# Bluetooth_LMC9830SM.net
KiCad netlist of a schematic drawn in Altium Designer
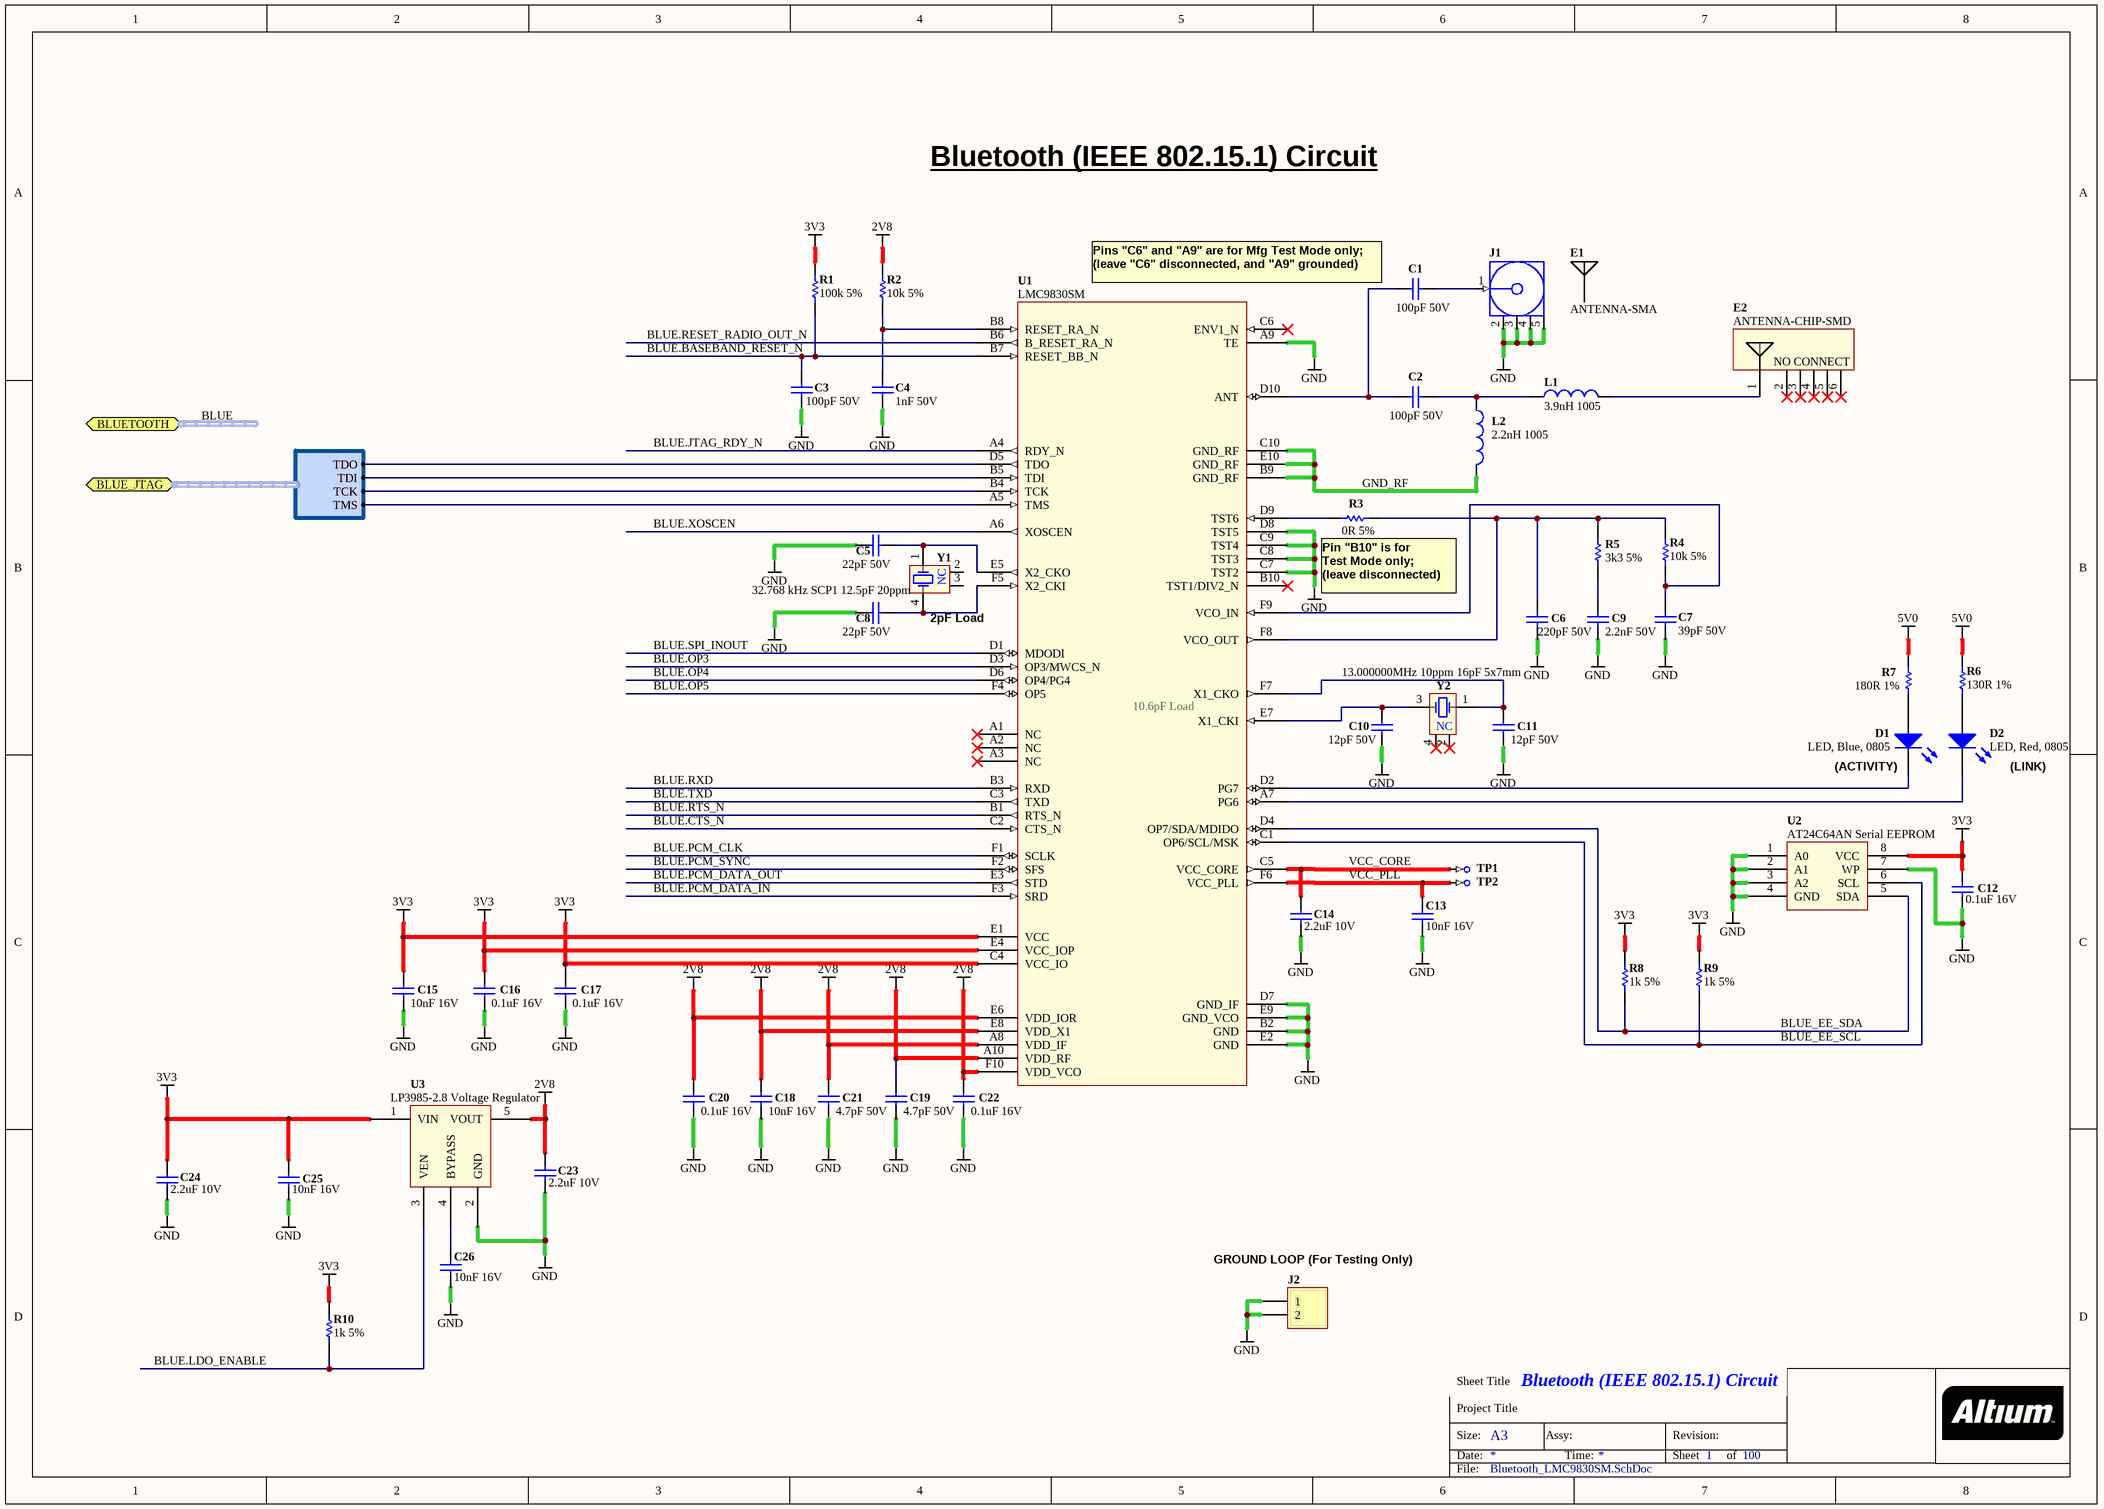
[diagram p0: Bluetooth_LMC9830SM.SchDoc]

(export (version "E")
  (design (tool "Eeschema 10.0.6"))
  (components
    (comp (ref "C1")
      (value "100pF 50V")
      (footprint "CAPC1005-STAR")
      (description "Capacitor, Ceramic, 100pF 5% 50V 0402 (1005) COG")
      (fields (field (name "TOLERANCE") "5 %"))
      (libsource (lib "AltiumDesignLibrary") (part "CAP-NP"))
    )
    (comp (ref "C2")
      (value "100pF 50V")
      (footprint "CAPC1005-STAR")
      (description "Capacitor, Ceramic, 100pF 5% 50V 0402 (1005) COG")
      (fields (field (name "TOLERANCE") "5 %"))
      (libsource (lib "AltiumDesignLibrary") (part "CAP-NP"))
    )
    (comp (ref "C3")
      (value "100pF 50V")
      (footprint "CAPC1005-STAR")
      (description "Capacitor, Ceramic, 100pF 5% 50V 0402 (1005) COG")
      (fields (field (name "TOLERANCE") "5 %"))
      (libsource (lib "AltiumDesignLibrary") (part "CAP-NP"))
    )
    (comp (ref "C4")
      (value "1nF 50V")
      (footprint "CAPC1005-STAR")
      (description "Capacitor, Ceramic, 1nF 10% 50V 0402 (1005) X7R")
      (fields (field (name "TOLERANCE") "10 %"))
      (libsource (lib "AltiumDesignLibrary") (part "CAP-NP"))
    )
    (comp (ref "C5")
      (value "22pF 50V")
      (footprint "CAPC1005-STAR")
      (description "Capacitor, Ceramic, 22pF 5% 50V 0402 (1005) COG")
      (fields (field (name "TOLERANCE") "5 %"))
      (libsource (lib "AltiumDesignLibrary") (part "CAP-NP"))
    )
    (comp (ref "C6")
      (value "220pF 50V")
      (footprint "CAPC1005-STAR")
      (description "Capacitor, Ceramic, 220pF 5% 50V 0402 (1005) COG")
      (fields (field (name "TOLERANCE") "5 %"))
      (libsource (lib "AltiumDesignLibrary") (part "CAP-NP"))
    )
    (comp (ref "C7")
      (value "39pF 50V")
      (footprint "CAPC1005-STAR")
      (description "Capacitor, Ceramic, 39pF 5% 50V 0402 (1005) COG")
      (fields (field (name "TOLERANCE") "5 %"))
      (libsource (lib "AltiumDesignLibrary") (part "CAP-NP"))
    )
    (comp (ref "C8")
      (value "22pF 50V")
      (footprint "CAPC1005-STAR")
      (description "Capacitor, Ceramic, 22pF 5% 50V 0402 (1005) COG")
      (fields (field (name "TOLERANCE") "5 %"))
      (libsource (lib "AltiumDesignLibrary") (part "CAP-NP"))
    )
    (comp (ref "C9")
      (value "2.2nF 50V")
      (footprint "CAPC1608-STAR")
      (description "Capacitor, Ceramic, 2.2nF 10% 50V 0603 (1608) X7R")
      (fields (field (name "TOLERANCE") "10 %"))
      (libsource (lib "AltiumDesignLibrary") (part "CAP-NP"))
    )
    (comp (ref "C10")
      (value "12pF 50V")
      (footprint "CAPC1005-STAR")
      (description "Capacitor, Ceramic, 12pF 2% 50V 0402 (1005) COG")
      (fields (field (name "TOLERANCE") "2 %"))
      (libsource (lib "AltiumDesignLibrary") (part "CAP-NP"))
    )
    (comp (ref "C11")
      (value "12pF 50V")
      (footprint "CAPC1005-STAR")
      (description "Capacitor, Ceramic, 12pF 2% 50V 0402 (1005) COG")
      (fields (field (name "TOLERANCE") "2 %"))
      (libsource (lib "AltiumDesignLibrary") (part "CAP-NP"))
    )
    (comp (ref "C12")
      (value "0.1uF 16V")
      (footprint "CAPC1005-STAR")
      (description "Capacitor, Ceramic, 0.1uF 10% 16V 0402 (1005) X7R")
      (fields (field (name "TOLERANCE") "10 %"))
      (libsource (lib "AltiumDesignLibrary") (part "CAP-NP"))
    )
    (comp (ref "C13")
      (value "10nF 16V")
      (footprint "CAPC1005-STAR")
      (description "Capacitor, Ceramic, 10nF 10% 16V 0402 (1005) X7R")
      (fields (field (name "TOLERANCE") "10 %"))
      (libsource (lib "AltiumDesignLibrary") (part "CAP-NP"))
    )
    (comp (ref "C14")
      (value "2.2uF 10V")
      (footprint "CAPC3216-STAR")
      (description "Capacitor, Ceramic, 2.2uF 10% 10V 1206 (3216) X7R")
      (fields (field (name "TOLERANCE") "10 %"))
      (libsource (lib "AltiumDesignLibrary") (part "CAP-NP"))
    )
    (comp (ref "C15")
      (value "10nF 16V")
      (footprint "CAPC1005-STAR")
      (description "Capacitor, Ceramic, 10nF 10% 16V 0402 (1005) X7R")
      (fields (field (name "TOLERANCE") "10 %"))
      (libsource (lib "AltiumDesignLibrary") (part "CAP-NP"))
    )
    (comp (ref "C16")
      (value "0.1uF 16V")
      (footprint "CAPC1005-STAR")
      (description "Capacitor, Ceramic, 0.1uF 10% 16V 0402 (1005) X7R")
      (fields (field (name "TOLERANCE") "10 %"))
      (libsource (lib "AltiumDesignLibrary") (part "CAP-NP"))
    )
    (comp (ref "C17")
      (value "0.1uF 16V")
      (footprint "CAPC1005-STAR")
      (description "Capacitor, Ceramic, 0.1uF 10% 16V 0402 (1005) X7R")
      (fields (field (name "TOLERANCE") "10 %"))
      (libsource (lib "AltiumDesignLibrary") (part "CAP-NP"))
    )
    (comp (ref "C18")
      (value "10nF 16V")
      (footprint "CAPC1005-STAR")
      (description "Capacitor, Ceramic, 10nF 10% 16V 0402 (1005) X7R")
      (fields (field (name "TOLERANCE") "10 %"))
      (libsource (lib "AltiumDesignLibrary") (part "CAP-NP"))
    )
    (comp (ref "C19")
      (value "4.7pF 50V")
      (footprint "CAPC1005-STAR")
      (description "Capacitor, Ceramic, 4.7pF 5% 50V 0402 (1005) COG")
      (fields (field (name "TOLERANCE") "5 %"))
      (libsource (lib "AltiumDesignLibrary") (part "CAP-NP"))
    )
    (comp (ref "C20")
      (value "0.1uF 16V")
      (footprint "CAPC1005-STAR")
      (description "Capacitor, Ceramic, 0.1uF 10% 16V 0402 (1005) X7R")
      (fields (field (name "TOLERANCE") "10 %"))
      (libsource (lib "AltiumDesignLibrary") (part "CAP-NP"))
    )
    (comp (ref "C21")
      (value "4.7pF 50V")
      (footprint "CAPC1005-STAR")
      (description "Capacitor, Ceramic, 4.7pF 5% 50V 0402 (1005) COG")
      (fields (field (name "TOLERANCE") "5 %"))
      (libsource (lib "AltiumDesignLibrary") (part "CAP-NP"))
    )
    (comp (ref "C22")
      (value "0.1uF 16V")
      (footprint "CAPC1005-STAR")
      (description "Capacitor, Ceramic, 0.1uF 10% 16V 0402 (1005) X7R")
      (fields (field (name "TOLERANCE") "10 %"))
      (libsource (lib "AltiumDesignLibrary") (part "CAP-NP"))
    )
    (comp (ref "C23")
      (value "2.2uF 10V")
      (footprint "CAPC3216-STAR")
      (description "Capacitor, Ceramic, 2.2uF 10% 10V 1206 (3216) X7R")
      (fields (field (name "TOLERANCE") "10 %"))
      (libsource (lib "AltiumDesignLibrary") (part "CAP-NP"))
    )
    (comp (ref "C24")
      (value "2.2uF 10V")
      (footprint "CAPC3216-STAR")
      (description "Capacitor, Ceramic, 2.2uF 10% 10V 1206 (3216) X7R")
      (fields (field (name "TOLERANCE") "10 %"))
      (libsource (lib "AltiumDesignLibrary") (part "CAP-NP"))
    )
    (comp (ref "C25")
      (value "10nF 16V")
      (footprint "CAPC1005-STAR")
      (description "Capacitor, Ceramic, 10nF 10% 16V 0402 (1005) X7R")
      (fields (field (name "TOLERANCE") "10 %"))
      (libsource (lib "AltiumDesignLibrary") (part "CAP-NP"))
    )
    (comp (ref "C26")
      (value "10nF 16V")
      (footprint "CAPC1005-STAR")
      (description "Capacitor, Ceramic, 10nF 10% 16V 0402 (1005) X7R")
      (fields (field (name "TOLERANCE") "10 %"))
      (libsource (lib "AltiumDesignLibrary") (part "CAP-NP"))
    )
    (comp (ref "D1")
      (value "LED, Blue, 0805")
      (footprint "LED2012-STAR")
      (description "LED, Blue 0805 (2012)")
      (libsource (lib "AltiumDesignLibrary") (part "DIO-LED-1S"))
    )
    (comp (ref "D2")
      (value "LED, Red, 0805")
      (footprint "LED2012-STAR")
      (description "LED, Red 0805 (2012) HSMH-C170")
      (libsource (lib "AltiumDesignLibrary") (part "DIO-LED-1S"))
    )
    (comp (ref "E1")
      (value "ANTENNA-SMA")
      (description "Antenna, 2.45GHz 1/4 Wave 50R SMA Antenna")
      (libsource (lib "AltiumDesignLibrary") (part "ANTENNA-0-PIN"))
    )
    (comp (ref "E2")
      (value "ANTENNA-CHIP-SMD")
      (footprint "ANTENNA-2-45GHZ-6PIN")
      (description "Antenna, 2.45GHz Chip SMD 5.5 X 7.35MM")
      (libsource (lib "AltiumDesignLibrary") (part "ANTENNA-6-PIN"))
    )
    (comp (ref "J1")
      (value "SMA 5-pin Vertical Jack 50R")
      (footprint "HDR-SMA-THD-5-PIN")
      (description "SMA RF Coaxial PCB Connector, 5-pin Through-hole, Vertical Mount Socket, 50 ohm impedance")
      (libsource (lib "AltiumDesignLibrary") (part "CON-HDR-COAXIAL-5-PIN"))
    )
    (comp (ref "J2")
      (value "1x2 HEADER MALE")
      (footprint "HDR1X2")
      (description "Header IDC, 2 x 1 Pin Vertical 2.54mm Pitch (Non-Boxed, Male)")
      (libsource (lib "AltiumDesignLibrary") (part "CON-HDR-1x2-STR"))
    )
    (comp (ref "L1")
      (value "3.9nH 1005")
      (footprint "INDC1005")
      (description "Inductor, Chip 3.9nH 300mA DCR=0.18 ohm, High Frequency 0402 (1005)")
      (libsource (lib "AltiumDesignLibrary") (part "IND"))
    )
    (comp (ref "L2")
      (value "2.2nH 1005")
      (footprint "INDC1005")
      (description "Inductor, Chip 2.2nH 300mA DCR=0.12 ohm, High Frequency 0402 (1005)")
      (libsource (lib "AltiumDesignLibrary") (part "IND"))
    )
    (comp (ref "R1")
      (value "100k 5%")
      (footprint "RESC1005-STAR")
      (description "Resistor, 100k 5% 0402 (1005)")
      (fields (field (name "TOLERANCE") "5 %"))
      (libsource (lib "AltiumDesignLibrary") (part "RES"))
    )
    (comp (ref "R2")
      (value "10k 5%")
      (footprint "RESC1005-STAR")
      (description "Resistor, 10k 5% 0402 (1005)")
      (fields (field (name "TOLERANCE") "5 %"))
      (libsource (lib "AltiumDesignLibrary") (part "RES"))
    )
    (comp (ref "R3")
      (value "0R 5%")
      (footprint "RESC1005-STAR")
      (description "Resistor, 0R 5% 0402 (1005)")
      (fields (field (name "TOLERANCE") "5 %"))
      (libsource (lib "AltiumDesignLibrary") (part "RES"))
    )
    (comp (ref "R4")
      (value "10k 5%")
      (footprint "RESC1005-STAR")
      (description "Resistor, 10k 5% 0402 (1005)")
      (fields (field (name "TOLERANCE") "5 %"))
      (libsource (lib "AltiumDesignLibrary") (part "RES"))
    )
    (comp (ref "R5")
      (value "3k3 5%")
      (footprint "RESC1005-STAR")
      (description "Resistor, 3k3 5% 0402 (1005)")
      (fields (field (name "TOLERANCE") "5 %"))
      (libsource (lib "AltiumDesignLibrary") (part "RES"))
    )
    (comp (ref "R6")
      (value "130R 1%")
      (footprint "RESC1005-STAR")
      (description "Resistor, 130R 1% 0402 (1005)")
      (fields (field (name "TOLERANCE") "1 %"))
      (libsource (lib "AltiumDesignLibrary") (part "RES"))
    )
    (comp (ref "R7")
      (value "180R 1%")
      (footprint "RESC1005-STAR")
      (description "Resistor, 180R 1% 0402 (1005)")
      (fields (field (name "TOLERANCE") "1 %"))
      (libsource (lib "AltiumDesignLibrary") (part "RES"))
    )
    (comp (ref "R8")
      (value "1k 5%")
      (footprint "RESC1005-STAR")
      (description "Resistor, 1k 5% 0402 (1005)")
      (fields (field (name "TOLERANCE") "5 %"))
      (libsource (lib "AltiumDesignLibrary") (part "RES"))
    )
    (comp (ref "R9")
      (value "1k 5%")
      (footprint "RESC1005-STAR")
      (description "Resistor, 1k 5% 0402 (1005)")
      (fields (field (name "TOLERANCE") "5 %"))
      (libsource (lib "AltiumDesignLibrary") (part "RES"))
    )
    (comp (ref "R10")
      (value "1k 5%")
      (footprint "RESC1005-STAR")
      (description "Resistor, 1k 5% 0402 (1005)")
      (fields (field (name "TOLERANCE") "5 %"))
      (libsource (lib "AltiumDesignLibrary") (part "RES"))
    )
    (comp (ref "TP1")
      (value "TestPin")
      (footprint "TestPin")
      (description "Test Point, PCB Mount with Silkscreen Box")
      (libsource (lib "AltiumDesignLibrary") (part "TestPin"))
    )
    (comp (ref "TP2")
      (value "TestPin")
      (footprint "TestPin")
      (description "Test Point, PCB Mount with Silkscreen Box")
      (libsource (lib "AltiumDesignLibrary") (part "TestPin"))
    )
    (comp (ref "U1")
      (value "LMC9830SM")
      (footprint "BGA80P9X6-60")
      (description "LMC9830SM, 2.45GHz Bluetooth Serial Port Module, BGA60")
      (libsource (lib "AltiumDesignLibrary") (part "IC-LMX9830SM"))
    )
    (comp (ref "U2")
      (value "AT24C64AN Serial EEPROM")
      (footprint "SOIC8-150-BODY")
      (description "AT24C64AN Two-Wire Serial EEPROM 2.7-5.5V SOIC-8 (JEDEC)")
      (libsource (lib "AltiumDesignLibrary") (part "IC-AT24C64"))
    )
    (comp (ref "U3")
      (value "LP3985-2.8 Voltage Regulator")
      (footprint "SOT-23-5")
      (description "LP3985IM5-2.8, 2V8 Voltage Regulator, Low-Noise Ultra Low-Dropout, 150mA, SOT-23-5")
      (libsource (lib "AltiumDesignLibrary") (part "IC-LP3985"))
    )
    (comp (ref "Y1")
      (value "32.768 kHz SCP1 12.5pF 20ppm")
      (footprint "XTAL-SCP1")
      (description "Crystal, 32.768 kHz, Surface Mount SCP1, 12.5pF, 20ppm")
      (libsource (lib "AltiumDesignLibrary") (part "CRYSTAL-4PINS-1-TO-4"))
    )
    (comp (ref "Y2")
      (value "13.000000MHz 10ppm 16pF 5x7mm")
      (footprint "XTAL-7X5")
      (description "Crystal, 13.000000MHz, 5x7mm, 10ppm 10ppm 16pF")
      (libsource (lib "AltiumDesignLibrary") (part "CRYSTAL-4PINS-1-TO-3"))
    )
  )
  (nets
    (net (code "3") (name "/BLUE.BASEBAND_RESET_N") (class "Default")
      (node (ref "C3") (pin "2") (pinfunction "2_2") (pintype "passive"))
      (node (ref "R1") (pin "2") (pinfunction "2_2") (pintype "passive"))
      (node (ref "U1") (pin "B7") (pinfunction "RESET_BB_N_B7") (pintype "input"))
    )
    (net (code "4") (name "/BLUE.CTS_N") (class "Default")
      (node (ref "U1") (pin "C2") (pinfunction "CTS_N_C2") (pintype "input"))
    )
    (net (code "5") (name "/BLUE.JTAG_RDY_N") (class "Default")
      (node (ref "U1") (pin "A4") (pinfunction "RDY_N_A4") (pintype "output"))
    )
    (net (code "6") (name "/BLUE.LDO_ENABLE") (class "Default")
      (node (ref "R10") (pin "2") (pinfunction "2_2") (pintype "passive"))
      (node (ref "U3") (pin "3") (pinfunction "VEN_3") (pintype "passive"))
    )
    (net (code "7") (name "/BLUE.OP3") (class "Default")
      (node (ref "U1") (pin "D3") (pinfunction "OP3/MWCS_N_D3") (pintype "input"))
    )
    (net (code "8") (name "/BLUE.OP4") (class "Default")
      (node (ref "U1") (pin "D6") (pinfunction "OP4/PG4_D6") (pintype "bidirectional"))
    )
    (net (code "9") (name "/BLUE.OP5") (class "Default")
      (node (ref "U1") (pin "F4") (pinfunction "OP5_F4") (pintype "bidirectional"))
    )
    (net (code "10") (name "/BLUE.PCM_CLK") (class "Default")
      (node (ref "U1") (pin "F1") (pinfunction "SCLK_F1") (pintype "bidirectional"))
    )
    (net (code "11") (name "/BLUE.PCM_DATA_IN") (class "Default")
      (node (ref "U1") (pin "F3") (pinfunction "SRD_F3") (pintype "input"))
    )
    (net (code "12") (name "/BLUE.PCM_DATA_OUT") (class "Default")
      (node (ref "U1") (pin "E3") (pinfunction "STD_E3") (pintype "output"))
    )
    (net (code "13") (name "/BLUE.PCM_SYNC") (class "Default")
      (node (ref "U1") (pin "F2") (pinfunction "SFS_F2") (pintype "bidirectional"))
    )
    (net (code "14") (name "/BLUE.RESET_RADIO_OUT_N") (class "Default")
      (node (ref "U1") (pin "B6") (pinfunction "B_RESET_RA_N_B6") (pintype "output"))
    )
    (net (code "15") (name "/BLUE.RTS_N") (class "Default")
      (node (ref "U1") (pin "B1") (pinfunction "RTS_N_B1") (pintype "output"))
    )
    (net (code "16") (name "/BLUE.RXD") (class "Default")
      (node (ref "U1") (pin "B3") (pinfunction "RXD_B3") (pintype "input"))
    )
    (net (code "17") (name "/BLUE.SPI_INOUT") (class "Default")
      (node (ref "U1") (pin "D1") (pinfunction "MDODI_D1") (pintype "bidirectional"))
    )
    (net (code "18") (name "/BLUE.TXD") (class "Default")
      (node (ref "U1") (pin "C3") (pinfunction "TXD_C3") (pintype "output"))
    )
    (net (code "19") (name "/BLUE.XOSCEN") (class "Default")
      (node (ref "U1") (pin "A6") (pinfunction "XOSCEN_A6") (pintype "output"))
    )
    (net (code "20") (name "/BLUE_EE_SCL") (class "Default")
      (node (ref "R9") (pin "2") (pinfunction "2_2") (pintype "passive"))
      (node (ref "U1") (pin "C1") (pinfunction "OP6/SCL/MSK_C1") (pintype "bidirectional"))
      (node (ref "U2") (pin "6") (pinfunction "SCL_6") (pintype "passive"))
    )
    (net (code "21") (name "/BLUE_EE_SDA") (class "Default")
      (node (ref "R8") (pin "2") (pinfunction "2_2") (pintype "passive"))
      (node (ref "U1") (pin "D4") (pinfunction "OP7/SDA/MDIDO_D4") (pintype "bidirectional"))
      (node (ref "U2") (pin "5") (pinfunction "SDA_5") (pintype "passive"))
    )
    (net (code "22") (name "/GND_RF") (class "Default")
      (node (ref "L2") (pin "2") (pinfunction "2_2") (pintype "passive"))
      (node (ref "U1") (pin "B9") (pinfunction "GND_RF_B9") (pintype "power_in"))
      (node (ref "U1") (pin "C10") (pinfunction "GND_RF_C10") (pintype "power_in"))
      (node (ref "U1") (pin "E10") (pinfunction "GND_RF_E10") (pintype "power_in"))
    )
    (net (code "23") (name "/TCK") (class "Default")
      (node (ref "U1") (pin "B4") (pinfunction "TCK_B4") (pintype "input"))
    )
    (net (code "24") (name "/TDI") (class "Default")
      (node (ref "U1") (pin "B5") (pinfunction "TDI_B5") (pintype "input"))
    )
    (net (code "25") (name "/TDO") (class "Default")
      (node (ref "U1") (pin "D5") (pinfunction "TDO_D5") (pintype "output"))
    )
    (net (code "26") (name "/TMS") (class "Default")
      (node (ref "U1") (pin "A5") (pinfunction "TMS_A5") (pintype "input"))
    )
    (net (code "27") (name "/VCC_CORE") (class "Default")
      (node (ref "C14") (pin "1") (pinfunction "1_1") (pintype "passive"))
      (node (ref "TP1") (pin "1") (pinfunction "1_1") (pintype "input"))
      (node (ref "U1") (pin "C5") (pinfunction "VCC_CORE_C5") (pintype "output"))
    )
    (net (code "28") (name "/VCC_PLL") (class "Default")
      (node (ref "C13") (pin "1") (pinfunction "1_1") (pintype "passive"))
      (node (ref "TP2") (pin "1") (pinfunction "1_1") (pintype "input"))
      (node (ref "U1") (pin "F6") (pinfunction "VCC_PLL_F6") (pintype "output"))
    )
    (net (code "31") (name "2V8") (class "Default")
      (node (ref "C18") (pin "1") (pinfunction "1_1") (pintype "passive"))
      (node (ref "C19") (pin "1") (pinfunction "1_1") (pintype "passive"))
      (node (ref "C20") (pin "1") (pinfunction "1_1") (pintype "passive"))
      (node (ref "C21") (pin "1") (pinfunction "1_1") (pintype "passive"))
      (node (ref "C22") (pin "1") (pinfunction "1_1") (pintype "passive"))
      (node (ref "C23") (pin "1") (pinfunction "1_1") (pintype "passive"))
      (node (ref "R2") (pin "1") (pinfunction "1_1") (pintype "passive"))
      (node (ref "U1") (pin "A10") (pinfunction "VDD_RF_A10") (pintype "passive"))
      (node (ref "U1") (pin "A8") (pinfunction "VDD_IF_A8") (pintype "passive"))
      (node (ref "U1") (pin "E6") (pinfunction "VDD_IOR_E6") (pintype "passive"))
      (node (ref "U1") (pin "E8") (pinfunction "VDD_X1_E8") (pintype "passive"))
      (node (ref "U1") (pin "F10") (pinfunction "VDD_VCO_F10") (pintype "passive"))
      (node (ref "U3") (pin "5") (pinfunction "VOUT_5") (pintype "passive"))
    )
    (net (code "32") (name "3V3") (class "Default")
      (node (ref "C12") (pin "1") (pinfunction "1_1") (pintype "passive"))
      (node (ref "C15") (pin "1") (pinfunction "1_1") (pintype "passive"))
      (node (ref "C16") (pin "1") (pinfunction "1_1") (pintype "passive"))
      (node (ref "C17") (pin "1") (pinfunction "1_1") (pintype "passive"))
      (node (ref "C24") (pin "1") (pinfunction "1_1") (pintype "passive"))
      (node (ref "C25") (pin "1") (pinfunction "1_1") (pintype "passive"))
      (node (ref "R1") (pin "1") (pinfunction "1_1") (pintype "passive"))
      (node (ref "R10") (pin "1") (pinfunction "1_1") (pintype "passive"))
      (node (ref "R8") (pin "1") (pinfunction "1_1") (pintype "passive"))
      (node (ref "R9") (pin "1") (pinfunction "1_1") (pintype "passive"))
      (node (ref "U1") (pin "C4") (pinfunction "VCC_IO_C4") (pintype "power_in"))
      (node (ref "U1") (pin "E1") (pinfunction "VCC_E1") (pintype "power_in"))
      (node (ref "U1") (pin "E4") (pinfunction "VCC_IOP_E4") (pintype "power_in"))
      (node (ref "U2") (pin "8") (pinfunction "VCC_8") (pintype "passive"))
      (node (ref "U3") (pin "1") (pinfunction "VIN_1") (pintype "passive"))
    )
    (net (code "33") (name "5V0") (class "Default")
      (node (ref "R6") (pin "1") (pinfunction "1_1") (pintype "passive"))
      (node (ref "R7") (pin "1") (pinfunction "1_1") (pintype "passive"))
    )
    (net (code "34") (name "GND") (class "Default")
      (node (ref "C10") (pin "2") (pinfunction "2_2") (pintype "passive"))
      (node (ref "C11") (pin "2") (pinfunction "2_2") (pintype "passive"))
      (node (ref "C12") (pin "2") (pinfunction "2_2") (pintype "passive"))
      (node (ref "C13") (pin "2") (pinfunction "2_2") (pintype "passive"))
      (node (ref "C14") (pin "2") (pinfunction "2_2") (pintype "passive"))
      (node (ref "C15") (pin "2") (pinfunction "2_2") (pintype "passive"))
      (node (ref "C16") (pin "2") (pinfunction "2_2") (pintype "passive"))
      (node (ref "C17") (pin "2") (pinfunction "2_2") (pintype "passive"))
      (node (ref "C18") (pin "2") (pinfunction "2_2") (pintype "passive"))
      (node (ref "C19") (pin "2") (pinfunction "2_2") (pintype "passive"))
      (node (ref "C20") (pin "2") (pinfunction "2_2") (pintype "passive"))
      (node (ref "C21") (pin "2") (pinfunction "2_2") (pintype "passive"))
      (node (ref "C22") (pin "2") (pinfunction "2_2") (pintype "passive"))
      (node (ref "C23") (pin "2") (pinfunction "2_2") (pintype "passive"))
      (node (ref "C24") (pin "2") (pinfunction "2_2") (pintype "passive"))
      (node (ref "C25") (pin "2") (pinfunction "2_2") (pintype "passive"))
      (node (ref "C26") (pin "2") (pinfunction "2_2") (pintype "passive"))
      (node (ref "C3") (pin "1") (pinfunction "1_1") (pintype "passive"))
      (node (ref "C4") (pin "2") (pinfunction "2_2") (pintype "passive"))
      (node (ref "C5") (pin "1") (pinfunction "1_1") (pintype "passive"))
      (node (ref "C6") (pin "2") (pinfunction "2_2") (pintype "passive"))
      (node (ref "C7") (pin "2") (pinfunction "2_2") (pintype "passive"))
      (node (ref "C8") (pin "1") (pinfunction "1_1") (pintype "passive"))
      (node (ref "C9") (pin "2") (pinfunction "2_2") (pintype "passive"))
      (node (ref "J1") (pin "2") (pinfunction "GND_2") (pintype "passive"))
      (node (ref "J1") (pin "3") (pinfunction "GND_3") (pintype "passive"))
      (node (ref "J1") (pin "4") (pinfunction "GND_4") (pintype "passive"))
      (node (ref "J1") (pin "5") (pinfunction "GND_5") (pintype "passive"))
      (node (ref "J2") (pin "1") (pinfunction "1_1") (pintype "passive"))
      (node (ref "J2") (pin "2") (pinfunction "2_2") (pintype "passive"))
      (node (ref "U1") (pin "A9") (pinfunction "TE_A9") (pintype "passive"))
      (node (ref "U1") (pin "B2") (pinfunction "GND_B2") (pintype "power_in"))
      (node (ref "U1") (pin "C7") (pinfunction "TST2_C7") (pintype "passive"))
      (node (ref "U1") (pin "C8") (pinfunction "TST3_C8") (pintype "passive"))
      (node (ref "U1") (pin "C9") (pinfunction "TST4_C9") (pintype "passive"))
      (node (ref "U1") (pin "D7") (pinfunction "GND_IF_D7") (pintype "power_in"))
      (node (ref "U1") (pin "D8") (pinfunction "TST5_D8") (pintype "passive"))
      (node (ref "U1") (pin "E2") (pinfunction "GND_E2") (pintype "power_in"))
      (node (ref "U1") (pin "E9") (pinfunction "GND_VCO_E9") (pintype "power_in"))
      (node (ref "U2") (pin "1") (pinfunction "A0_1") (pintype "passive"))
      (node (ref "U2") (pin "2") (pinfunction "A1_2") (pintype "passive"))
      (node (ref "U2") (pin "3") (pinfunction "A2_3") (pintype "passive"))
      (node (ref "U2") (pin "4") (pinfunction "GND_4") (pintype "passive"))
      (node (ref "U2") (pin "7") (pinfunction "WP_7") (pintype "passive"))
      (node (ref "U3") (pin "2") (pinfunction "GND_2") (pintype "passive"))
    )
    (net (code "35") (name "Net-(C2-Pad2)") (class "Default")
      (node (ref "C2") (pin "2") (pinfunction "2_2") (pintype "passive"))
      (node (ref "L1") (pin "1") (pinfunction "1_1") (pintype "passive"))
      (node (ref "L2") (pin "1") (pinfunction "1_1") (pintype "passive"))
    )
    (net (code "36") (name "Net-(C9-Pad1)") (class "Default")
      (node (ref "C9") (pin "1") (pinfunction "1_1") (pintype "passive"))
      (node (ref "R5") (pin "2") (pinfunction "2_2") (pintype "passive"))
    )
    (net (code "37") (name "Net-(D1-A)") (class "Default")
      (node (ref "D1") (pin "1") (pinfunction "A_1") (pintype "passive"))
      (node (ref "R7") (pin "2") (pinfunction "2_2") (pintype "passive"))
    )
    (net (code "38") (name "Net-(D1-K)") (class "Default")
      (node (ref "D1") (pin "2") (pinfunction "K_2") (pintype "passive"))
      (node (ref "U1") (pin "D2") (pinfunction "PG7_D2") (pintype "bidirectional"))
    )
    (net (code "39") (name "Net-(D2-A)") (class "Default")
      (node (ref "D2") (pin "1") (pinfunction "A_1") (pintype "passive"))
      (node (ref "R6") (pin "2") (pinfunction "2_2") (pintype "passive"))
    )
    (net (code "40") (name "Net-(D2-K)") (class "Default")
      (node (ref "D2") (pin "2") (pinfunction "K_2") (pintype "passive"))
      (node (ref "U1") (pin "A7") (pinfunction "PG6_A7") (pintype "bidirectional"))
    )
    (net (code "41") (name "Net-(E2-Pad1)") (class "Default")
      (node (ref "E2") (pin "1") (pinfunction "1_1") (pintype "passive"))
      (node (ref "L1") (pin "2") (pinfunction "2_2") (pintype "passive"))
    )
    (net (code "42") (name "Net-(J1-Signal)") (class "Default")
      (node (ref "C1") (pin "2") (pinfunction "2_2") (pintype "passive"))
      (node (ref "J1") (pin "1") (pinfunction "Signal_1") (pintype "input"))
    )
    (net (code "43") (name "Net-(U1-ANT)") (class "Default")
      (node (ref "C1") (pin "1") (pinfunction "1_1") (pintype "passive"))
      (node (ref "C2") (pin "1") (pinfunction "1_1") (pintype "passive"))
      (node (ref "U1") (pin "D10") (pinfunction "ANT_D10") (pintype "bidirectional"))
    )
    (net (code "44") (name "Net-(U1-RESET_RA_N)") (class "Default")
      (node (ref "C4") (pin "1") (pinfunction "1_1") (pintype "passive"))
      (node (ref "R2") (pin "2") (pinfunction "2_2") (pintype "passive"))
      (node (ref "U1") (pin "B8") (pinfunction "RESET_RA_N_B8") (pintype "input"))
    )
    (net (code "45") (name "Net-(U1-TST6)") (class "Default")
      (node (ref "R3") (pin "1") (pinfunction "1_1") (pintype "passive"))
      (node (ref "U1") (pin "D9") (pinfunction "TST6_D9") (pintype "input"))
    )
    (net (code "46") (name "Net-(U1-VCO_IN)") (class "Default")
      (node (ref "C7") (pin "1") (pinfunction "1_1") (pintype "passive"))
      (node (ref "R4") (pin "2") (pinfunction "2_2") (pintype "passive"))
      (node (ref "U1") (pin "F9") (pinfunction "VCO_IN_F9") (pintype "input"))
    )
    (net (code "47") (name "Net-(U1-VCO_OUT)") (class "Default")
      (node (ref "C6") (pin "1") (pinfunction "1_1") (pintype "passive"))
      (node (ref "R3") (pin "2") (pinfunction "2_2") (pintype "passive"))
      (node (ref "R4") (pin "1") (pinfunction "1_1") (pintype "passive"))
      (node (ref "R5") (pin "1") (pinfunction "1_1") (pintype "passive"))
      (node (ref "U1") (pin "F8") (pinfunction "VCO_OUT_F8") (pintype "output"))
    )
    (net (code "48") (name "Net-(U1-X1_CKI)") (class "Default")
      (node (ref "C10") (pin "1") (pinfunction "1_1") (pintype "passive"))
      (node (ref "U1") (pin "E7") (pinfunction "X1_CKI_E7") (pintype "input"))
      (node (ref "Y2") (pin "3") (pinfunction "X2_3") (pintype "passive"))
    )
    (net (code "49") (name "Net-(U1-X1_CKO)") (class "Default")
      (node (ref "C11") (pin "1") (pinfunction "1_1") (pintype "passive"))
      (node (ref "U1") (pin "F7") (pinfunction "X1_CKO_F7") (pintype "output"))
      (node (ref "Y2") (pin "1") (pinfunction "X1_1") (pintype "passive"))
    )
    (net (code "50") (name "Net-(U1-X2_CKI)") (class "Default")
      (node (ref "C8") (pin "2") (pinfunction "2_2") (pintype "passive"))
      (node (ref "U1") (pin "F5") (pinfunction "X2_CKI_F5") (pintype "input"))
      (node (ref "Y1") (pin "4") (pinfunction "X2_4") (pintype "passive"))
    )
    (net (code "51") (name "Net-(U1-X2_CKO)") (class "Default")
      (node (ref "C5") (pin "2") (pinfunction "2_2") (pintype "passive"))
      (node (ref "U1") (pin "E5") (pinfunction "X2_CKO_E5") (pintype "output"))
      (node (ref "Y1") (pin "1") (pinfunction "X1_1") (pintype "passive"))
    )
    (net (code "52") (name "Net-(U3-BYPASS)") (class "Default")
      (node (ref "C26") (pin "1") (pinfunction "1_1") (pintype "passive"))
      (node (ref "U3") (pin "4") (pinfunction "BYPASS_4") (pintype "passive"))
    )
    (net (code "53") (name "unconnected-(E2-Pad2)") (class "Default")
      (node (ref "E2") (pin "2") (pinfunction "2_2") (pintype "passive+no_connect"))
    )
    (net (code "54") (name "unconnected-(E2-Pad3)") (class "Default")
      (node (ref "E2") (pin "3") (pinfunction "3_3") (pintype "passive+no_connect"))
    )
    (net (code "55") (name "unconnected-(E2-Pad4)") (class "Default")
      (node (ref "E2") (pin "4") (pinfunction "4_4") (pintype "passive+no_connect"))
    )
    (net (code "56") (name "unconnected-(E2-Pad5)") (class "Default")
      (node (ref "E2") (pin "5") (pinfunction "5_5") (pintype "passive+no_connect"))
    )
    (net (code "57") (name "unconnected-(E2-Pad6)") (class "Default")
      (node (ref "E2") (pin "6") (pinfunction "6_6") (pintype "passive+no_connect"))
    )
    (net (code "58") (name "unconnected-(U1-ENV1_N-PadC6)") (class "Default")
      (node (ref "U1") (pin "C6") (pinfunction "ENV1_N_C6") (pintype "input+no_connect"))
    )
    (net (code "59") (name "unconnected-(U1-NC-PadA1)") (class "Default")
      (node (ref "U1") (pin "A1") (pinfunction "NC_A1") (pintype "passive+no_connect"))
    )
    (net (code "60") (name "unconnected-(U1-NC-PadA2)") (class "Default")
      (node (ref "U1") (pin "A2") (pinfunction "NC_A2") (pintype "passive+no_connect"))
    )
    (net (code "61") (name "unconnected-(U1-NC-PadA3)") (class "Default")
      (node (ref "U1") (pin "A3") (pinfunction "NC_A3") (pintype "passive+no_connect"))
    )
    (net (code "62") (name "unconnected-(U1-TST1{slash}DIV2_N-PadB10)") (class "Default")
      (node (ref "U1") (pin "B10") (pinfunction "TST1/DIV2_N_B10") (pintype "passive+no_connect"))
    )
    (net (code "63") (name "unconnected-(Y1-NC-Pad2)") (class "Default")
      (node (ref "Y1") (pin "2") (pinfunction "NC_2") (pintype "passive"))
    )
    (net (code "64") (name "unconnected-(Y1-NC-Pad3)") (class "Default")
      (node (ref "Y1") (pin "3") (pinfunction "NC_3") (pintype "passive"))
    )
    (net (code "65") (name "unconnected-(Y2-NC-Pad2)") (class "Default")
      (node (ref "Y2") (pin "2") (pinfunction "NC_2") (pintype "passive+no_connect"))
    )
    (net (code "66") (name "unconnected-(Y2-NC-Pad4)") (class "Default")
      (node (ref "Y2") (pin "4") (pinfunction "NC_4") (pintype "passive+no_connect"))
    )
  )
)
